# schematic.net
KiCad netlist of a schematic drawn in EasyEDA
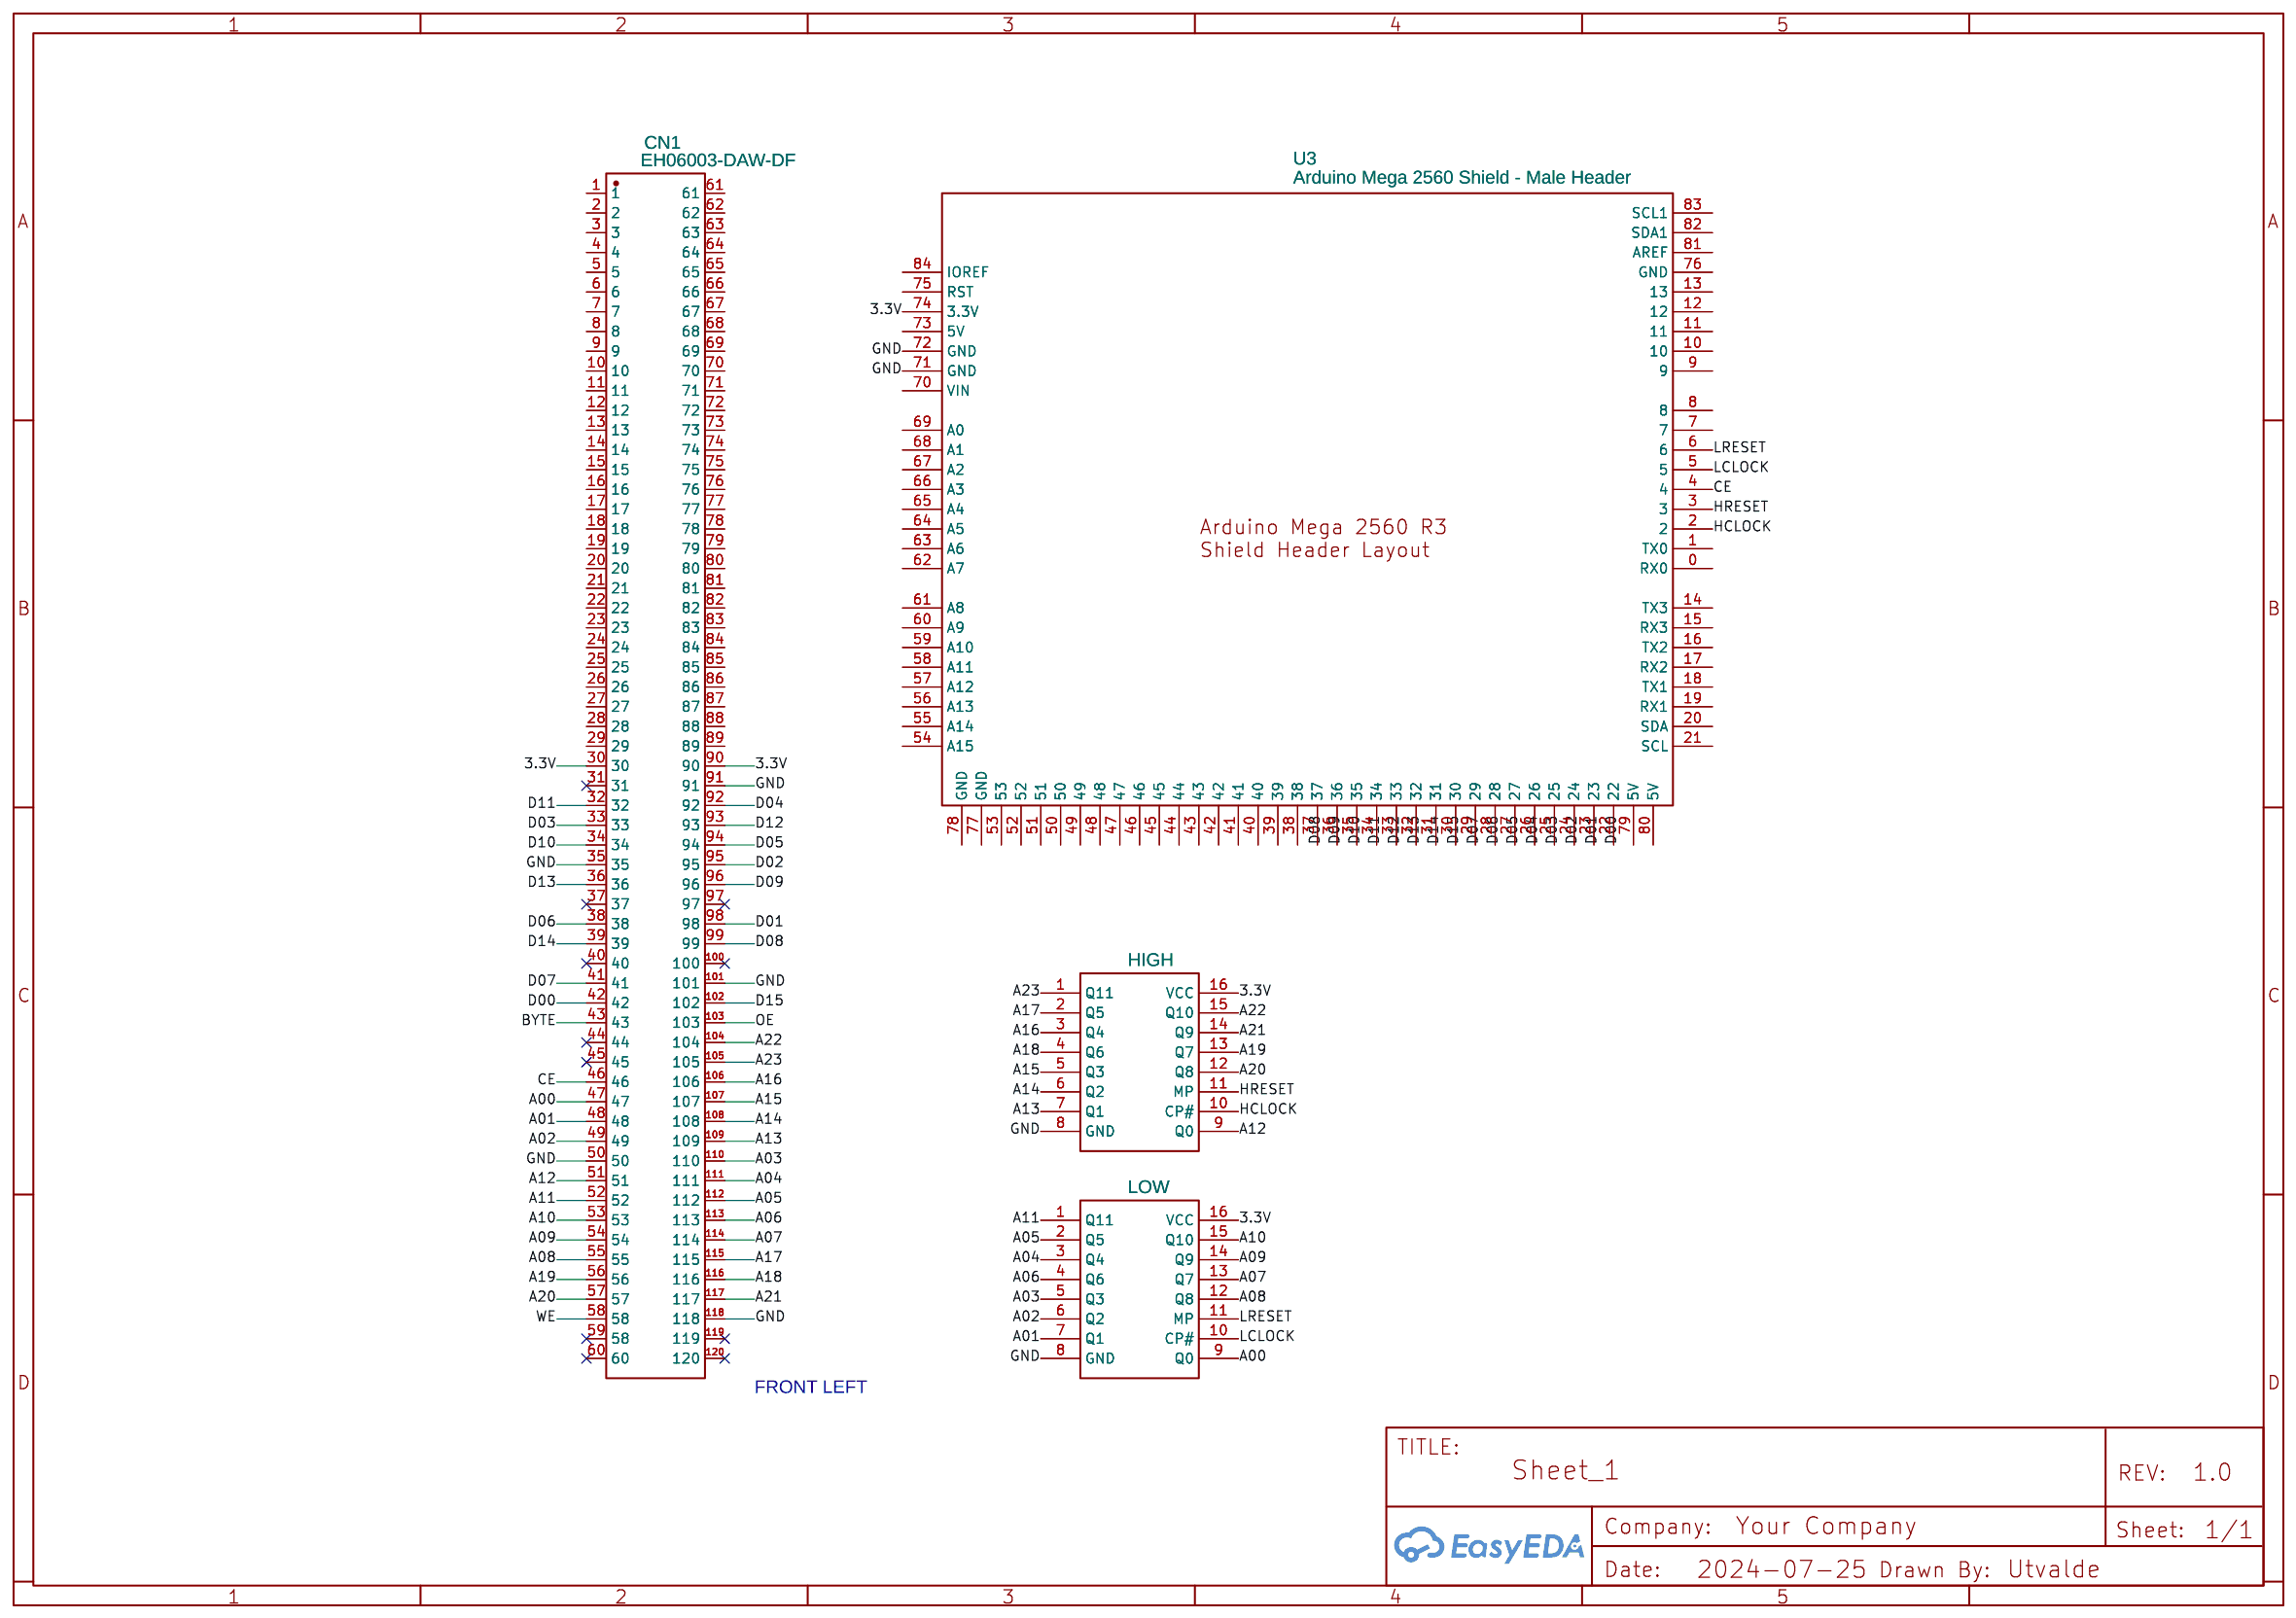
[diagram p0: schematic sheet]

(export (version "E")
  (design (tool "Eeschema 10.0.6"))
  (components
    (comp (ref "CN1")
      (value "EH06003-DAW-DF")
      (fields (field (name "Manufacturer") "FOXCONN(富士康)"))
      (libsource (lib "") (part "EH06003-DAW-DF"))
    )
    (comp (ref "U1")
      (value "LOW")
      (fields (field (name "Manufacturer Part") "74HC4040D,653") (field (name "Manufacturer") "Nexperia(安世)"))
      (libsource (lib "") (part "74HC4040D,653"))
    )
    (comp (ref "U2")
      (value "HIGH")
      (fields (field (name "Manufacturer Part") "74HC4040D,653") (field (name "Manufacturer") "Nexperia(安世)"))
      (libsource (lib "") (part "74HC4040D,653"))
    )
    (comp (ref "U3")
      (value "Arduino Mega 2560 Shield - Male Header")
      (fields (field (name "Manufacturer Part") "None"))
      (libsource (lib "") (part "Arduino Mega 2560 Shield - Male Header"))
    )
  )
  (nets
    (net (code "1") (name "/3.3V") (class "Default")
      (node (ref "CN1") (pin "30") (pinfunction "30_30") (pintype "unspecified"))
      (node (ref "CN1") (pin "90") (pinfunction "90_90") (pintype "unspecified"))
      (node (ref "U1") (pin "16") (pinfunction "VCC_16") (pintype "unspecified"))
      (node (ref "U2") (pin "16") (pinfunction "VCC_16") (pintype "unspecified"))
      (node (ref "U3") (pin "74") (pinfunction "3.3V_74") (pintype "unspecified"))
    )
    (net (code "2") (name "/A00") (class "Default")
      (node (ref "CN1") (pin "47") (pinfunction "47_47") (pintype "unspecified"))
      (node (ref "U1") (pin "9") (pinfunction "Q0_9") (pintype "unspecified"))
    )
    (net (code "3") (name "/A01") (class "Default")
      (node (ref "CN1") (pin "48") (pinfunction "48_48") (pintype "unspecified"))
      (node (ref "U1") (pin "7") (pinfunction "Q1_7") (pintype "unspecified"))
    )
    (net (code "4") (name "/A02") (class "Default")
      (node (ref "CN1") (pin "49") (pinfunction "49_49") (pintype "unspecified"))
      (node (ref "U1") (pin "6") (pinfunction "Q2_6") (pintype "unspecified"))
    )
    (net (code "5") (name "/A03") (class "Default")
      (node (ref "CN1") (pin "110") (pinfunction "110_110") (pintype "unspecified"))
      (node (ref "U1") (pin "5") (pinfunction "Q3_5") (pintype "unspecified"))
    )
    (net (code "6") (name "/A04") (class "Default")
      (node (ref "CN1") (pin "111") (pinfunction "111_111") (pintype "unspecified"))
      (node (ref "U1") (pin "3") (pinfunction "Q4_3") (pintype "unspecified"))
    )
    (net (code "7") (name "/A05") (class "Default")
      (node (ref "CN1") (pin "112") (pinfunction "112_112") (pintype "unspecified"))
      (node (ref "U1") (pin "2") (pinfunction "Q5_2") (pintype "unspecified"))
    )
    (net (code "8") (name "/A06") (class "Default")
      (node (ref "CN1") (pin "113") (pinfunction "113_113") (pintype "unspecified"))
      (node (ref "U1") (pin "4") (pinfunction "Q6_4") (pintype "unspecified"))
    )
    (net (code "9") (name "/A07") (class "Default")
      (node (ref "CN1") (pin "114") (pinfunction "114_114") (pintype "unspecified"))
      (node (ref "U1") (pin "13") (pinfunction "Q7_13") (pintype "unspecified"))
    )
    (net (code "10") (name "/A08") (class "Default")
      (node (ref "CN1") (pin "55") (pinfunction "55_55") (pintype "unspecified"))
      (node (ref "U1") (pin "12") (pinfunction "Q8_12") (pintype "unspecified"))
    )
    (net (code "11") (name "/A09") (class "Default")
      (node (ref "CN1") (pin "54") (pinfunction "54_54") (pintype "unspecified"))
      (node (ref "U1") (pin "14") (pinfunction "Q9_14") (pintype "unspecified"))
    )
    (net (code "12") (name "/A10") (class "Default")
      (node (ref "CN1") (pin "53") (pinfunction "53_53") (pintype "unspecified"))
      (node (ref "U1") (pin "15") (pinfunction "Q10_15") (pintype "unspecified"))
    )
    (net (code "13") (name "/A11") (class "Default")
      (node (ref "CN1") (pin "52") (pinfunction "52_52") (pintype "unspecified"))
      (node (ref "U1") (pin "1") (pinfunction "Q11_1") (pintype "unspecified"))
    )
    (net (code "14") (name "/A12") (class "Default")
      (node (ref "CN1") (pin "51") (pinfunction "51_51") (pintype "unspecified"))
      (node (ref "U2") (pin "9") (pinfunction "Q0_9") (pintype "unspecified"))
    )
    (net (code "15") (name "/A13") (class "Default")
      (node (ref "CN1") (pin "109") (pinfunction "109_109") (pintype "unspecified"))
      (node (ref "U2") (pin "7") (pinfunction "Q1_7") (pintype "unspecified"))
    )
    (net (code "16") (name "/A14") (class "Default")
      (node (ref "CN1") (pin "108") (pinfunction "108_108") (pintype "unspecified"))
      (node (ref "U2") (pin "6") (pinfunction "Q2_6") (pintype "unspecified"))
    )
    (net (code "17") (name "/A15") (class "Default")
      (node (ref "CN1") (pin "107") (pinfunction "107_107") (pintype "unspecified"))
      (node (ref "U2") (pin "5") (pinfunction "Q3_5") (pintype "unspecified"))
    )
    (net (code "18") (name "/A16") (class "Default")
      (node (ref "CN1") (pin "106") (pinfunction "106_106") (pintype "unspecified"))
      (node (ref "U2") (pin "3") (pinfunction "Q4_3") (pintype "unspecified"))
    )
    (net (code "19") (name "/A17") (class "Default")
      (node (ref "CN1") (pin "115") (pinfunction "115_115") (pintype "unspecified"))
      (node (ref "U2") (pin "2") (pinfunction "Q5_2") (pintype "unspecified"))
    )
    (net (code "20") (name "/A18") (class "Default")
      (node (ref "CN1") (pin "116") (pinfunction "116_116") (pintype "unspecified"))
      (node (ref "U2") (pin "4") (pinfunction "Q6_4") (pintype "unspecified"))
    )
    (net (code "21") (name "/A19") (class "Default")
      (node (ref "CN1") (pin "56") (pinfunction "56_56") (pintype "unspecified"))
      (node (ref "U2") (pin "13") (pinfunction "Q7_13") (pintype "unspecified"))
    )
    (net (code "22") (name "/A20") (class "Default")
      (node (ref "CN1") (pin "57") (pinfunction "57_57") (pintype "unspecified"))
      (node (ref "U2") (pin "12") (pinfunction "Q8_12") (pintype "unspecified"))
    )
    (net (code "23") (name "/A21") (class "Default")
      (node (ref "CN1") (pin "117") (pinfunction "117_117") (pintype "unspecified"))
      (node (ref "U2") (pin "14") (pinfunction "Q9_14") (pintype "unspecified"))
    )
    (net (code "24") (name "/A22") (class "Default")
      (node (ref "CN1") (pin "104") (pinfunction "104_104") (pintype "unspecified"))
      (node (ref "U2") (pin "15") (pinfunction "Q10_15") (pintype "unspecified"))
    )
    (net (code "25") (name "/A23") (class "Default")
      (node (ref "CN1") (pin "105") (pinfunction "105_105") (pintype "unspecified"))
      (node (ref "U2") (pin "1") (pinfunction "Q11_1") (pintype "unspecified"))
    )
    (net (code "26") (name "/BYTE") (class "Default")
      (node (ref "CN1") (pin "43") (pinfunction "43_43") (pintype "unspecified"))
    )
    (net (code "27") (name "/CE") (class "Default")
      (node (ref "CN1") (pin "46") (pinfunction "46_46") (pintype "unspecified"))
      (node (ref "U3") (pin "4") (pinfunction "4_4") (pintype "unspecified"))
    )
    (net (code "28") (name "/D00") (class "Default")
      (node (ref "CN1") (pin "42") (pinfunction "42_42") (pintype "unspecified"))
      (node (ref "U3") (pin "22") (pinfunction "22_22") (pintype "unspecified"))
    )
    (net (code "29") (name "/D01") (class "Default")
      (node (ref "CN1") (pin "98") (pinfunction "98_98") (pintype "unspecified"))
      (node (ref "U3") (pin "23") (pinfunction "23_23") (pintype "unspecified"))
    )
    (net (code "30") (name "/D02") (class "Default")
      (node (ref "CN1") (pin "95") (pinfunction "95_95") (pintype "unspecified"))
      (node (ref "U3") (pin "24") (pinfunction "24_24") (pintype "unspecified"))
    )
    (net (code "31") (name "/D03") (class "Default")
      (node (ref "CN1") (pin "33") (pinfunction "33_33") (pintype "unspecified"))
      (node (ref "U3") (pin "25") (pinfunction "25_25") (pintype "unspecified"))
    )
    (net (code "32") (name "/D04") (class "Default")
      (node (ref "CN1") (pin "92") (pinfunction "92_92") (pintype "unspecified"))
      (node (ref "U3") (pin "26") (pinfunction "26_26") (pintype "unspecified"))
    )
    (net (code "33") (name "/D05") (class "Default")
      (node (ref "CN1") (pin "94") (pinfunction "94_94") (pintype "unspecified"))
      (node (ref "U3") (pin "27") (pinfunction "27_27") (pintype "unspecified"))
    )
    (net (code "34") (name "/D06") (class "Default")
      (node (ref "CN1") (pin "38") (pinfunction "38_38") (pintype "unspecified"))
      (node (ref "U3") (pin "28") (pinfunction "28_28") (pintype "unspecified"))
    )
    (net (code "35") (name "/D07") (class "Default")
      (node (ref "CN1") (pin "41") (pinfunction "41_41") (pintype "unspecified"))
      (node (ref "U3") (pin "29") (pinfunction "29_29") (pintype "unspecified"))
    )
    (net (code "36") (name "/D08") (class "Default")
      (node (ref "CN1") (pin "99") (pinfunction "99_99") (pintype "unspecified"))
      (node (ref "U3") (pin "37") (pinfunction "37_37") (pintype "unspecified"))
    )
    (net (code "37") (name "/D09") (class "Default")
      (node (ref "CN1") (pin "96") (pinfunction "96_96") (pintype "unspecified"))
      (node (ref "U3") (pin "36") (pinfunction "36_36") (pintype "unspecified"))
    )
    (net (code "38") (name "/D10") (class "Default")
      (node (ref "CN1") (pin "34") (pinfunction "34_34") (pintype "unspecified"))
      (node (ref "U3") (pin "35") (pinfunction "35_35") (pintype "unspecified"))
    )
    (net (code "39") (name "/D11") (class "Default")
      (node (ref "CN1") (pin "32") (pinfunction "32_32") (pintype "unspecified"))
      (node (ref "U3") (pin "34") (pinfunction "34_34") (pintype "unspecified"))
    )
    (net (code "40") (name "/D12") (class "Default")
      (node (ref "CN1") (pin "93") (pinfunction "93_93") (pintype "unspecified"))
      (node (ref "U3") (pin "33") (pinfunction "33_33") (pintype "unspecified"))
    )
    (net (code "41") (name "/D13") (class "Default")
      (node (ref "CN1") (pin "36") (pinfunction "36_36") (pintype "unspecified"))
      (node (ref "U3") (pin "32") (pinfunction "32_32") (pintype "unspecified"))
    )
    (net (code "42") (name "/D14") (class "Default")
      (node (ref "CN1") (pin "39") (pinfunction "39_39") (pintype "unspecified"))
      (node (ref "U3") (pin "31") (pinfunction "31_31") (pintype "unspecified"))
    )
    (net (code "43") (name "/D15") (class "Default")
      (node (ref "CN1") (pin "102") (pinfunction "102_102") (pintype "unspecified"))
      (node (ref "U3") (pin "30") (pinfunction "30_30") (pintype "unspecified"))
    )
    (net (code "44") (name "/GND") (class "Default")
      (node (ref "CN1") (pin "101") (pinfunction "101_101") (pintype "unspecified"))
      (node (ref "CN1") (pin "118") (pinfunction "118_118") (pintype "unspecified"))
      (node (ref "CN1") (pin "35") (pinfunction "35_35") (pintype "unspecified"))
      (node (ref "CN1") (pin "50") (pinfunction "50_50") (pintype "unspecified"))
      (node (ref "CN1") (pin "91") (pinfunction "91_91") (pintype "unspecified"))
      (node (ref "U1") (pin "8") (pinfunction "GND_8") (pintype "unspecified"))
      (node (ref "U2") (pin "8") (pinfunction "GND_8") (pintype "unspecified"))
      (node (ref "U3") (pin "71") (pinfunction "GND_71") (pintype "unspecified"))
      (node (ref "U3") (pin "72") (pinfunction "GND_72") (pintype "unspecified"))
    )
    (net (code "45") (name "/HCLOCK") (class "Default")
      (node (ref "U2") (pin "10") (pinfunction "CP#_10") (pintype "unspecified"))
      (node (ref "U3") (pin "2") (pinfunction "2_2") (pintype "unspecified"))
    )
    (net (code "46") (name "/HRESET") (class "Default")
      (node (ref "U2") (pin "11") (pinfunction "MP_11") (pintype "unspecified"))
      (node (ref "U3") (pin "3") (pinfunction "3_3") (pintype "unspecified"))
    )
    (net (code "47") (name "/LCLOCK") (class "Default")
      (node (ref "U1") (pin "10") (pinfunction "CP#_10") (pintype "unspecified"))
      (node (ref "U3") (pin "5") (pinfunction "5_5") (pintype "unspecified"))
    )
    (net (code "48") (name "/LRESET") (class "Default")
      (node (ref "U1") (pin "11") (pinfunction "MP_11") (pintype "unspecified"))
      (node (ref "U3") (pin "6") (pinfunction "6_6") (pintype "unspecified"))
    )
    (net (code "49") (name "/OE") (class "Default")
      (node (ref "CN1") (pin "103") (pinfunction "103_103") (pintype "unspecified"))
    )
    (net (code "50") (name "/WE") (class "Default")
      (node (ref "CN1") (pin "58") (pinfunction "58_58") (pintype "unspecified"))
    )
    (net (code "51") (name "unconnected-(CN1-58-Pad59)") (class "Default")
      (node (ref "CN1") (pin "59") (pinfunction "58_59") (pintype "unspecified+no_connect"))
    )
    (net (code "52") (name "unconnected-(CN1-Pad1)") (class "Default")
      (node (ref "CN1") (pin "1") (pinfunction "1_1") (pintype "unspecified"))
    )
    (net (code "53") (name "unconnected-(CN1-Pad2)") (class "Default")
      (node (ref "CN1") (pin "2") (pinfunction "2_2") (pintype "unspecified"))
    )
    (net (code "54") (name "unconnected-(CN1-Pad3)") (class "Default")
      (node (ref "CN1") (pin "3") (pinfunction "3_3") (pintype "unspecified"))
    )
    (net (code "55") (name "unconnected-(CN1-Pad4)") (class "Default")
      (node (ref "CN1") (pin "4") (pinfunction "4_4") (pintype "unspecified"))
    )
    (net (code "56") (name "unconnected-(CN1-Pad5)") (class "Default")
      (node (ref "CN1") (pin "5") (pinfunction "5_5") (pintype "unspecified"))
    )
    (net (code "57") (name "unconnected-(CN1-Pad6)") (class "Default")
      (node (ref "CN1") (pin "6") (pinfunction "6_6") (pintype "unspecified"))
    )
    (net (code "58") (name "unconnected-(CN1-Pad7)") (class "Default")
      (node (ref "CN1") (pin "7") (pinfunction "7_7") (pintype "unspecified"))
    )
    (net (code "59") (name "unconnected-(CN1-Pad8)") (class "Default")
      (node (ref "CN1") (pin "8") (pinfunction "8_8") (pintype "unspecified"))
    )
    (net (code "60") (name "unconnected-(CN1-Pad9)") (class "Default")
      (node (ref "CN1") (pin "9") (pinfunction "9_9") (pintype "unspecified"))
    )
    (net (code "61") (name "unconnected-(CN1-Pad10)") (class "Default")
      (node (ref "CN1") (pin "10") (pinfunction "10_10") (pintype "unspecified"))
    )
    (net (code "62") (name "unconnected-(CN1-Pad11)") (class "Default")
      (node (ref "CN1") (pin "11") (pinfunction "11_11") (pintype "unspecified"))
    )
    (net (code "63") (name "unconnected-(CN1-Pad12)") (class "Default")
      (node (ref "CN1") (pin "12") (pinfunction "12_12") (pintype "unspecified"))
    )
    (net (code "64") (name "unconnected-(CN1-Pad13)") (class "Default")
      (node (ref "CN1") (pin "13") (pinfunction "13_13") (pintype "unspecified"))
    )
    (net (code "65") (name "unconnected-(CN1-Pad14)") (class "Default")
      (node (ref "CN1") (pin "14") (pinfunction "14_14") (pintype "unspecified"))
    )
    (net (code "66") (name "unconnected-(CN1-Pad15)") (class "Default")
      (node (ref "CN1") (pin "15") (pinfunction "15_15") (pintype "unspecified"))
    )
    (net (code "67") (name "unconnected-(CN1-Pad16)") (class "Default")
      (node (ref "CN1") (pin "16") (pinfunction "16_16") (pintype "unspecified"))
    )
    (net (code "68") (name "unconnected-(CN1-Pad17)") (class "Default")
      (node (ref "CN1") (pin "17") (pinfunction "17_17") (pintype "unspecified"))
    )
    (net (code "69") (name "unconnected-(CN1-Pad18)") (class "Default")
      (node (ref "CN1") (pin "18") (pinfunction "18_18") (pintype "unspecified"))
    )
    (net (code "70") (name "unconnected-(CN1-Pad19)") (class "Default")
      (node (ref "CN1") (pin "19") (pinfunction "19_19") (pintype "unspecified"))
    )
    (net (code "71") (name "unconnected-(CN1-Pad20)") (class "Default")
      (node (ref "CN1") (pin "20") (pinfunction "20_20") (pintype "unspecified"))
    )
    (net (code "72") (name "unconnected-(CN1-Pad21)") (class "Default")
      (node (ref "CN1") (pin "21") (pinfunction "21_21") (pintype "unspecified"))
    )
    (net (code "73") (name "unconnected-(CN1-Pad22)") (class "Default")
      (node (ref "CN1") (pin "22") (pinfunction "22_22") (pintype "unspecified"))
    )
    (net (code "74") (name "unconnected-(CN1-Pad23)") (class "Default")
      (node (ref "CN1") (pin "23") (pinfunction "23_23") (pintype "unspecified"))
    )
    (net (code "75") (name "unconnected-(CN1-Pad24)") (class "Default")
      (node (ref "CN1") (pin "24") (pinfunction "24_24") (pintype "unspecified"))
    )
    (net (code "76") (name "unconnected-(CN1-Pad25)") (class "Default")
      (node (ref "CN1") (pin "25") (pinfunction "25_25") (pintype "unspecified"))
    )
    (net (code "77") (name "unconnected-(CN1-Pad26)") (class "Default")
      (node (ref "CN1") (pin "26") (pinfunction "26_26") (pintype "unspecified"))
    )
    (net (code "78") (name "unconnected-(CN1-Pad27)") (class "Default")
      (node (ref "CN1") (pin "27") (pinfunction "27_27") (pintype "unspecified"))
    )
    (net (code "79") (name "unconnected-(CN1-Pad28)") (class "Default")
      (node (ref "CN1") (pin "28") (pinfunction "28_28") (pintype "unspecified"))
    )
    (net (code "80") (name "unconnected-(CN1-Pad29)") (class "Default")
      (node (ref "CN1") (pin "29") (pinfunction "29_29") (pintype "unspecified"))
    )
    (net (code "81") (name "unconnected-(CN1-Pad31)") (class "Default")
      (node (ref "CN1") (pin "31") (pinfunction "31_31") (pintype "unspecified+no_connect"))
    )
    (net (code "82") (name "unconnected-(CN1-Pad37)") (class "Default")
      (node (ref "CN1") (pin "37") (pinfunction "37_37") (pintype "unspecified+no_connect"))
    )
    (net (code "83") (name "unconnected-(CN1-Pad40)") (class "Default")
      (node (ref "CN1") (pin "40") (pinfunction "40_40") (pintype "unspecified+no_connect"))
    )
    (net (code "84") (name "unconnected-(CN1-Pad44)") (class "Default")
      (node (ref "CN1") (pin "44") (pinfunction "44_44") (pintype "unspecified+no_connect"))
    )
    (net (code "85") (name "unconnected-(CN1-Pad45)") (class "Default")
      (node (ref "CN1") (pin "45") (pinfunction "45_45") (pintype "unspecified+no_connect"))
    )
    (net (code "86") (name "unconnected-(CN1-Pad60)") (class "Default")
      (node (ref "CN1") (pin "60") (pinfunction "60_60") (pintype "unspecified+no_connect"))
    )
    (net (code "87") (name "unconnected-(CN1-Pad61)") (class "Default")
      (node (ref "CN1") (pin "61") (pinfunction "61_61") (pintype "unspecified"))
    )
    (net (code "88") (name "unconnected-(CN1-Pad62)") (class "Default")
      (node (ref "CN1") (pin "62") (pinfunction "62_62") (pintype "unspecified"))
    )
    (net (code "89") (name "unconnected-(CN1-Pad63)") (class "Default")
      (node (ref "CN1") (pin "63") (pinfunction "63_63") (pintype "unspecified"))
    )
    (net (code "90") (name "unconnected-(CN1-Pad64)") (class "Default")
      (node (ref "CN1") (pin "64") (pinfunction "64_64") (pintype "unspecified"))
    )
    (net (code "91") (name "unconnected-(CN1-Pad65)") (class "Default")
      (node (ref "CN1") (pin "65") (pinfunction "65_65") (pintype "unspecified"))
    )
    (net (code "92") (name "unconnected-(CN1-Pad66)") (class "Default")
      (node (ref "CN1") (pin "66") (pinfunction "66_66") (pintype "unspecified"))
    )
    (net (code "93") (name "unconnected-(CN1-Pad67)") (class "Default")
      (node (ref "CN1") (pin "67") (pinfunction "67_67") (pintype "unspecified"))
    )
    (net (code "94") (name "unconnected-(CN1-Pad68)") (class "Default")
      (node (ref "CN1") (pin "68") (pinfunction "68_68") (pintype "unspecified"))
    )
    (net (code "95") (name "unconnected-(CN1-Pad69)") (class "Default")
      (node (ref "CN1") (pin "69") (pinfunction "69_69") (pintype "unspecified"))
    )
    (net (code "96") (name "unconnected-(CN1-Pad70)") (class "Default")
      (node (ref "CN1") (pin "70") (pinfunction "70_70") (pintype "unspecified"))
    )
    (net (code "97") (name "unconnected-(CN1-Pad71)") (class "Default")
      (node (ref "CN1") (pin "71") (pinfunction "71_71") (pintype "unspecified"))
    )
    (net (code "98") (name "unconnected-(CN1-Pad72)") (class "Default")
      (node (ref "CN1") (pin "72") (pinfunction "72_72") (pintype "unspecified"))
    )
    (net (code "99") (name "unconnected-(CN1-Pad73)") (class "Default")
      (node (ref "CN1") (pin "73") (pinfunction "73_73") (pintype "unspecified"))
    )
    (net (code "100") (name "unconnected-(CN1-Pad74)") (class "Default")
      (node (ref "CN1") (pin "74") (pinfunction "74_74") (pintype "unspecified"))
    )
    (net (code "101") (name "unconnected-(CN1-Pad75)") (class "Default")
      (node (ref "CN1") (pin "75") (pinfunction "75_75") (pintype "unspecified"))
    )
    (net (code "102") (name "unconnected-(CN1-Pad76)") (class "Default")
      (node (ref "CN1") (pin "76") (pinfunction "76_76") (pintype "unspecified"))
    )
    (net (code "103") (name "unconnected-(CN1-Pad77)") (class "Default")
      (node (ref "CN1") (pin "77") (pinfunction "77_77") (pintype "unspecified"))
    )
    (net (code "104") (name "unconnected-(CN1-Pad78)") (class "Default")
      (node (ref "CN1") (pin "78") (pinfunction "78_78") (pintype "unspecified"))
    )
    (net (code "105") (name "unconnected-(CN1-Pad79)") (class "Default")
      (node (ref "CN1") (pin "79") (pinfunction "79_79") (pintype "unspecified"))
    )
    (net (code "106") (name "unconnected-(CN1-Pad80)") (class "Default")
      (node (ref "CN1") (pin "80") (pinfunction "80_80") (pintype "unspecified"))
    )
    (net (code "107") (name "unconnected-(CN1-Pad81)") (class "Default")
      (node (ref "CN1") (pin "81") (pinfunction "81_81") (pintype "unspecified"))
    )
    (net (code "108") (name "unconnected-(CN1-Pad82)") (class "Default")
      (node (ref "CN1") (pin "82") (pinfunction "82_82") (pintype "unspecified"))
    )
    (net (code "109") (name "unconnected-(CN1-Pad83)") (class "Default")
      (node (ref "CN1") (pin "83") (pinfunction "83_83") (pintype "unspecified"))
    )
    (net (code "110") (name "unconnected-(CN1-Pad84)") (class "Default")
      (node (ref "CN1") (pin "84") (pinfunction "84_84") (pintype "unspecified"))
    )
    (net (code "111") (name "unconnected-(CN1-Pad85)") (class "Default")
      (node (ref "CN1") (pin "85") (pinfunction "85_85") (pintype "unspecified"))
    )
    (net (code "112") (name "unconnected-(CN1-Pad86)") (class "Default")
      (node (ref "CN1") (pin "86") (pinfunction "86_86") (pintype "unspecified"))
    )
    (net (code "113") (name "unconnected-(CN1-Pad87)") (class "Default")
      (node (ref "CN1") (pin "87") (pinfunction "87_87") (pintype "unspecified"))
    )
    (net (code "114") (name "unconnected-(CN1-Pad88)") (class "Default")
      (node (ref "CN1") (pin "88") (pinfunction "88_88") (pintype "unspecified"))
    )
    (net (code "115") (name "unconnected-(CN1-Pad89)") (class "Default")
      (node (ref "CN1") (pin "89") (pinfunction "89_89") (pintype "unspecified"))
    )
    (net (code "116") (name "unconnected-(CN1-Pad97)") (class "Default")
      (node (ref "CN1") (pin "97") (pinfunction "97_97") (pintype "unspecified+no_connect"))
    )
    (net (code "117") (name "unconnected-(CN1-Pad100)") (class "Default")
      (node (ref "CN1") (pin "100") (pinfunction "100_100") (pintype "unspecified+no_connect"))
    )
    (net (code "118") (name "unconnected-(CN1-Pad119)") (class "Default")
      (node (ref "CN1") (pin "119") (pinfunction "119_119") (pintype "unspecified+no_connect"))
    )
    (net (code "119") (name "unconnected-(CN1-Pad120)") (class "Default")
      (node (ref "CN1") (pin "120") (pinfunction "120_120") (pintype "unspecified+no_connect"))
    )
    (net (code "120") (name "unconnected-(U3-5V-Pad73)") (class "Default")
      (node (ref "U3") (pin "73") (pinfunction "5V_73") (pintype "unspecified"))
    )
    (net (code "121") (name "unconnected-(U3-5V-Pad79)") (class "Default")
      (node (ref "U3") (pin "79") (pinfunction "5V_79") (pintype "unspecified"))
    )
    (net (code "122") (name "unconnected-(U3-5V-Pad80)") (class "Default")
      (node (ref "U3") (pin "80") (pinfunction "5V_80") (pintype "unspecified"))
    )
    (net (code "123") (name "unconnected-(U3-A0-Pad69)") (class "Default")
      (node (ref "U3") (pin "69") (pinfunction "A0_69") (pintype "unspecified"))
    )
    (net (code "124") (name "unconnected-(U3-A1-Pad68)") (class "Default")
      (node (ref "U3") (pin "68") (pinfunction "A1_68") (pintype "unspecified"))
    )
    (net (code "125") (name "unconnected-(U3-A2-Pad67)") (class "Default")
      (node (ref "U3") (pin "67") (pinfunction "A2_67") (pintype "unspecified"))
    )
    (net (code "126") (name "unconnected-(U3-A3-Pad66)") (class "Default")
      (node (ref "U3") (pin "66") (pinfunction "A3_66") (pintype "unspecified"))
    )
    (net (code "127") (name "unconnected-(U3-A4-Pad65)") (class "Default")
      (node (ref "U3") (pin "65") (pinfunction "A4_65") (pintype "unspecified"))
    )
    (net (code "128") (name "unconnected-(U3-A5-Pad64)") (class "Default")
      (node (ref "U3") (pin "64") (pinfunction "A5_64") (pintype "unspecified"))
    )
    (net (code "129") (name "unconnected-(U3-A6-Pad63)") (class "Default")
      (node (ref "U3") (pin "63") (pinfunction "A6_63") (pintype "unspecified"))
    )
    (net (code "130") (name "unconnected-(U3-A7-Pad62)") (class "Default")
      (node (ref "U3") (pin "62") (pinfunction "A7_62") (pintype "unspecified"))
    )
    (net (code "131") (name "unconnected-(U3-A8-Pad61)") (class "Default")
      (node (ref "U3") (pin "61") (pinfunction "A8_61") (pintype "unspecified"))
    )
    (net (code "132") (name "unconnected-(U3-A9-Pad60)") (class "Default")
      (node (ref "U3") (pin "60") (pinfunction "A9_60") (pintype "unspecified"))
    )
    (net (code "133") (name "unconnected-(U3-A10-Pad59)") (class "Default")
      (node (ref "U3") (pin "59") (pinfunction "A10_59") (pintype "unspecified"))
    )
    (net (code "134") (name "unconnected-(U3-A11-Pad58)") (class "Default")
      (node (ref "U3") (pin "58") (pinfunction "A11_58") (pintype "unspecified"))
    )
    (net (code "135") (name "unconnected-(U3-A12-Pad57)") (class "Default")
      (node (ref "U3") (pin "57") (pinfunction "A12_57") (pintype "unspecified"))
    )
    (net (code "136") (name "unconnected-(U3-A13-Pad56)") (class "Default")
      (node (ref "U3") (pin "56") (pinfunction "A13_56") (pintype "unspecified"))
    )
    (net (code "137") (name "unconnected-(U3-A14-Pad55)") (class "Default")
      (node (ref "U3") (pin "55") (pinfunction "A14_55") (pintype "unspecified"))
    )
    (net (code "138") (name "unconnected-(U3-A15-Pad54)") (class "Default")
      (node (ref "U3") (pin "54") (pinfunction "A15_54") (pintype "unspecified"))
    )
    (net (code "139") (name "unconnected-(U3-AREF-Pad81)") (class "Default")
      (node (ref "U3") (pin "81") (pinfunction "AREF_81") (pintype "unspecified"))
    )
    (net (code "140") (name "unconnected-(U3-GND-Pad76)") (class "Default")
      (node (ref "U3") (pin "76") (pinfunction "GND_76") (pintype "unspecified"))
    )
    (net (code "141") (name "unconnected-(U3-GND-Pad77)") (class "Default")
      (node (ref "U3") (pin "77") (pinfunction "GND_77") (pintype "unspecified"))
    )
    (net (code "142") (name "unconnected-(U3-GND-Pad78)") (class "Default")
      (node (ref "U3") (pin "78") (pinfunction "GND_78") (pintype "unspecified"))
    )
    (net (code "143") (name "unconnected-(U3-IOREF-Pad84)") (class "Default")
      (node (ref "U3") (pin "84") (pinfunction "IOREF_84") (pintype "unspecified"))
    )
    (net (code "144") (name "unconnected-(U3-Pad7)") (class "Default")
      (node (ref "U3") (pin "7") (pinfunction "7_7") (pintype "unspecified"))
    )
    (net (code "145") (name "unconnected-(U3-Pad8)") (class "Default")
      (node (ref "U3") (pin "8") (pinfunction "8_8") (pintype "unspecified"))
    )
    (net (code "146") (name "unconnected-(U3-Pad9)") (class "Default")
      (node (ref "U3") (pin "9") (pinfunction "9_9") (pintype "unspecified"))
    )
    (net (code "147") (name "unconnected-(U3-Pad10)") (class "Default")
      (node (ref "U3") (pin "10") (pinfunction "10_10") (pintype "unspecified"))
    )
    (net (code "148") (name "unconnected-(U3-Pad11)") (class "Default")
      (node (ref "U3") (pin "11") (pinfunction "11_11") (pintype "unspecified"))
    )
    (net (code "149") (name "unconnected-(U3-Pad12)") (class "Default")
      (node (ref "U3") (pin "12") (pinfunction "12_12") (pintype "unspecified"))
    )
    (net (code "150") (name "unconnected-(U3-Pad13)") (class "Default")
      (node (ref "U3") (pin "13") (pinfunction "13_13") (pintype "unspecified"))
    )
    (net (code "151") (name "unconnected-(U3-Pad38)") (class "Default")
      (node (ref "U3") (pin "38") (pinfunction "38_38") (pintype "unspecified"))
    )
    (net (code "152") (name "unconnected-(U3-Pad39)") (class "Default")
      (node (ref "U3") (pin "39") (pinfunction "39_39") (pintype "unspecified"))
    )
    (net (code "153") (name "unconnected-(U3-Pad40)") (class "Default")
      (node (ref "U3") (pin "40") (pinfunction "40_40") (pintype "unspecified"))
    )
    (net (code "154") (name "unconnected-(U3-Pad41)") (class "Default")
      (node (ref "U3") (pin "41") (pinfunction "41_41") (pintype "unspecified"))
    )
    (net (code "155") (name "unconnected-(U3-Pad42)") (class "Default")
      (node (ref "U3") (pin "42") (pinfunction "42_42") (pintype "unspecified"))
    )
    (net (code "156") (name "unconnected-(U3-Pad43)") (class "Default")
      (node (ref "U3") (pin "43") (pinfunction "43_43") (pintype "unspecified"))
    )
    (net (code "157") (name "unconnected-(U3-Pad44)") (class "Default")
      (node (ref "U3") (pin "44") (pinfunction "44_44") (pintype "unspecified"))
    )
    (net (code "158") (name "unconnected-(U3-Pad45)") (class "Default")
      (node (ref "U3") (pin "45") (pinfunction "45_45") (pintype "unspecified"))
    )
    (net (code "159") (name "unconnected-(U3-Pad46)") (class "Default")
      (node (ref "U3") (pin "46") (pinfunction "46_46") (pintype "unspecified"))
    )
    (net (code "160") (name "unconnected-(U3-Pad47)") (class "Default")
      (node (ref "U3") (pin "47") (pinfunction "47_47") (pintype "unspecified"))
    )
    (net (code "161") (name "unconnected-(U3-Pad48)") (class "Default")
      (node (ref "U3") (pin "48") (pinfunction "48_48") (pintype "unspecified"))
    )
    (net (code "162") (name "unconnected-(U3-Pad49)") (class "Default")
      (node (ref "U3") (pin "49") (pinfunction "49_49") (pintype "unspecified"))
    )
    (net (code "163") (name "unconnected-(U3-Pad50)") (class "Default")
      (node (ref "U3") (pin "50") (pinfunction "50_50") (pintype "unspecified"))
    )
    (net (code "164") (name "unconnected-(U3-Pad51)") (class "Default")
      (node (ref "U3") (pin "51") (pinfunction "51_51") (pintype "unspecified"))
    )
    (net (code "165") (name "unconnected-(U3-Pad52)") (class "Default")
      (node (ref "U3") (pin "52") (pinfunction "52_52") (pintype "unspecified"))
    )
    (net (code "166") (name "unconnected-(U3-Pad53)") (class "Default")
      (node (ref "U3") (pin "53") (pinfunction "53_53") (pintype "unspecified"))
    )
    (net (code "167") (name "unconnected-(U3-RST-Pad75)") (class "Default")
      (node (ref "U3") (pin "75") (pinfunction "RST_75") (pintype "unspecified"))
    )
    (net (code "168") (name "unconnected-(U3-RX0-Pad0)") (class "Default")
      (node (ref "U3") (pin "0") (pinfunction "RX0_0") (pintype "unspecified"))
    )
    (net (code "169") (name "unconnected-(U3-RX1-Pad19)") (class "Default")
      (node (ref "U3") (pin "19") (pinfunction "RX1_19") (pintype "unspecified"))
    )
    (net (code "170") (name "unconnected-(U3-RX2-Pad17)") (class "Default")
      (node (ref "U3") (pin "17") (pinfunction "RX2_17") (pintype "unspecified"))
    )
    (net (code "171") (name "unconnected-(U3-RX3-Pad15)") (class "Default")
      (node (ref "U3") (pin "15") (pinfunction "RX3_15") (pintype "unspecified"))
    )
    (net (code "172") (name "unconnected-(U3-SCL-Pad21)") (class "Default")
      (node (ref "U3") (pin "21") (pinfunction "SCL_21") (pintype "unspecified"))
    )
    (net (code "173") (name "unconnected-(U3-SCL1-Pad83)") (class "Default")
      (node (ref "U3") (pin "83") (pinfunction "SCL1_83") (pintype "unspecified"))
    )
    (net (code "174") (name "unconnected-(U3-SDA-Pad20)") (class "Default")
      (node (ref "U3") (pin "20") (pinfunction "SDA_20") (pintype "unspecified"))
    )
    (net (code "175") (name "unconnected-(U3-SDA1-Pad82)") (class "Default")
      (node (ref "U3") (pin "82") (pinfunction "SDA1_82") (pintype "unspecified"))
    )
    (net (code "176") (name "unconnected-(U3-TX0-Pad1)") (class "Default")
      (node (ref "U3") (pin "1") (pinfunction "TX0_1") (pintype "unspecified"))
    )
    (net (code "177") (name "unconnected-(U3-TX1-Pad18)") (class "Default")
      (node (ref "U3") (pin "18") (pinfunction "TX1_18") (pintype "unspecified"))
    )
    (net (code "178") (name "unconnected-(U3-TX2-Pad16)") (class "Default")
      (node (ref "U3") (pin "16") (pinfunction "TX2_16") (pintype "unspecified"))
    )
    (net (code "179") (name "unconnected-(U3-TX3-Pad14)") (class "Default")
      (node (ref "U3") (pin "14") (pinfunction "TX3_14") (pintype "unspecified"))
    )
    (net (code "180") (name "unconnected-(U3-VIN-Pad70)") (class "Default")
      (node (ref "U3") (pin "70") (pinfunction "VIN_70") (pintype "unspecified"))
    )
  )
)
